# ADC.net
KiCad netlist of a schematic drawn in EAGLE
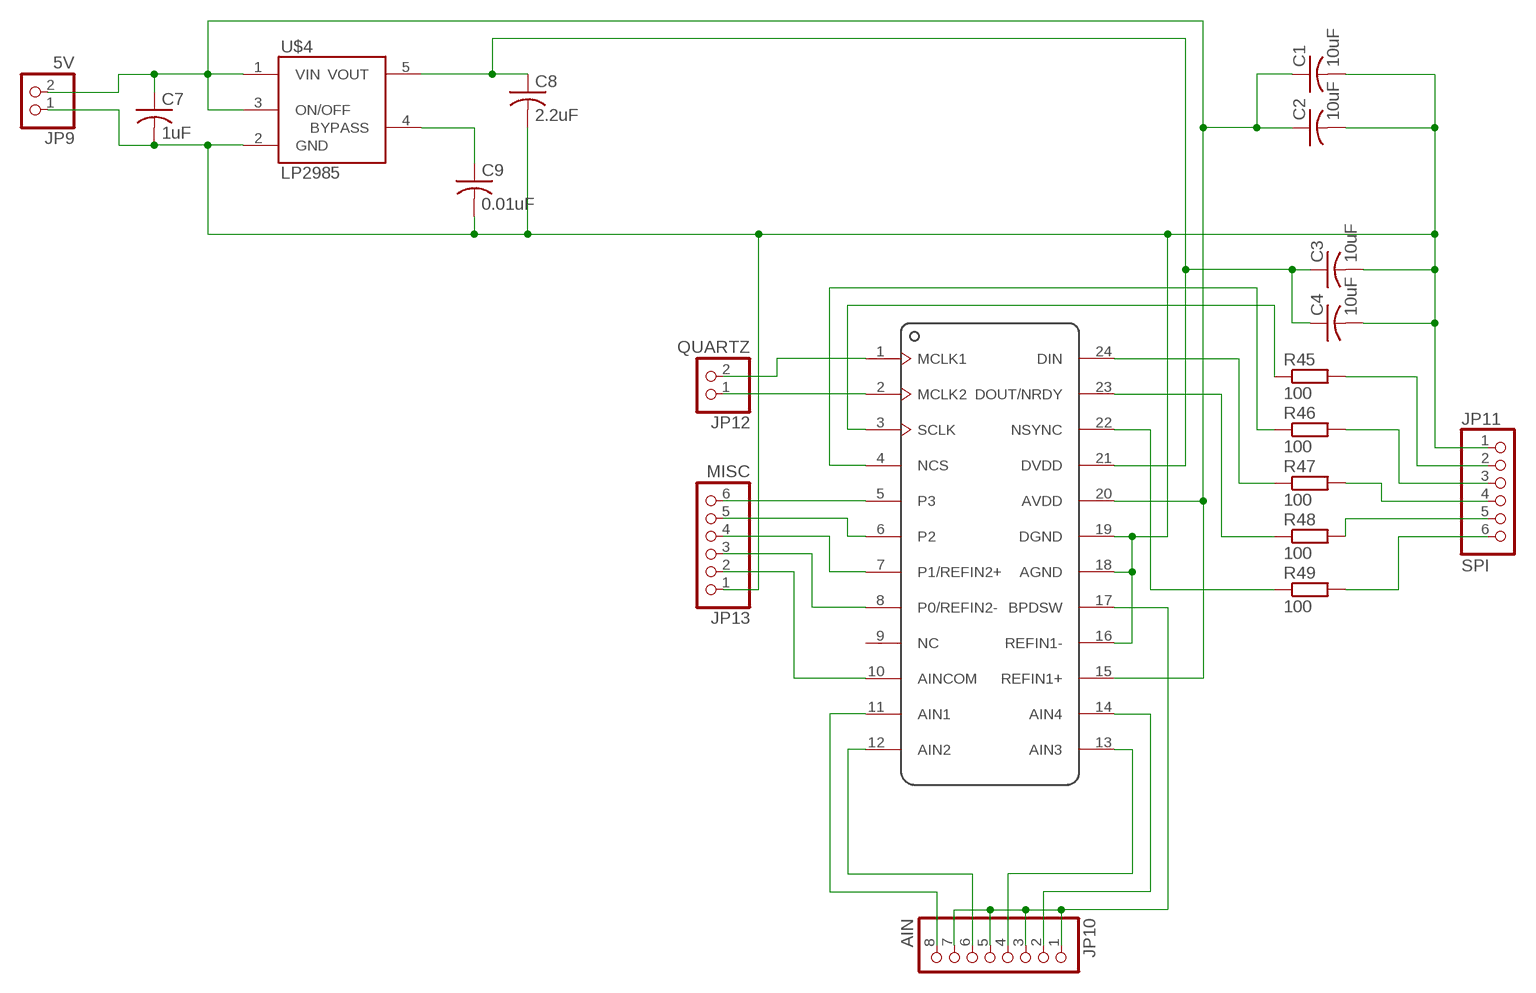
[diagram p0: schematic, sheet 1]

(export (version "E")
  (design (tool "Eeschema 10.0.6"))
  (components
    (comp (ref "C1")
      (value "10uF")
      (footprint "eagle-import:C0603")
      (libsource (lib "eagle-import") (part "C-USC0603"))
    )
    (comp (ref "C2")
      (value "10uF")
      (footprint "eagle-import:C0603")
      (libsource (lib "eagle-import") (part "C-USC0603"))
    )
    (comp (ref "C3")
      (value "10uF")
      (footprint "eagle-import:C0603")
      (libsource (lib "eagle-import") (part "C-USC0603"))
    )
    (comp (ref "C4")
      (value "10uF")
      (footprint "eagle-import:C0603")
      (libsource (lib "eagle-import") (part "C-USC0603"))
    )
    (comp (ref "C7")
      (value "1uF")
      (footprint "eagle-import:C0603")
      (libsource (lib "eagle-import") (part "C-USC0603"))
    )
    (comp (ref "C8")
      (value "2.2uF")
      (footprint "eagle-import:C0603")
      (libsource (lib "eagle-import") (part "C-USC0603"))
    )
    (comp (ref "C9")
      (value "0.01uF")
      (footprint "eagle-import:C0603")
      (libsource (lib "eagle-import") (part "C-USC0603"))
    )
    (comp (ref "JP9")
      (value "5V")
      (footprint "eagle-import:1X02")
      (libsource (lib "eagle-import") (part "PINHD-1X2"))
    )
    (comp (ref "JP10")
      (value "AIN")
      (footprint "eagle-import:1X08")
      (libsource (lib "eagle-import") (part "PINHD-1X8"))
    )
    (comp (ref "JP11")
      (value "SPI")
      (footprint "eagle-import:1X06")
      (libsource (lib "eagle-import") (part "PINHD-1X6"))
    )
    (comp (ref "JP12")
      (value "QUARTZ")
      (footprint "eagle-import:1X02")
      (libsource (lib "eagle-import") (part "PINHD-1X2"))
    )
    (comp (ref "JP13")
      (value "MISC")
      (footprint "eagle-import:1X06")
      (libsource (lib "eagle-import") (part "PINHD-1X6"))
    )
    (comp (ref "R45")
      (value "100")
      (footprint "eagle-import:R1206")
      (libsource (lib "eagle-import") (part "R-EU_R1206"))
    )
    (comp (ref "R46")
      (value "100")
      (footprint "eagle-import:R1206")
      (libsource (lib "eagle-import") (part "R-EU_R1206"))
    )
    (comp (ref "R47")
      (value "100")
      (footprint "eagle-import:R1206")
      (libsource (lib "eagle-import") (part "R-EU_R1206"))
    )
    (comp (ref "R48")
      (value "100")
      (footprint "eagle-import:R1206")
      (libsource (lib "eagle-import") (part "R-EU_R1206"))
    )
    (comp (ref "R49")
      (value "100")
      (footprint "eagle-import:R1206")
      (libsource (lib "eagle-import") (part "R-EU_R1206"))
    )
    (comp (ref "U$3")
      (value "AD7190")
      (footprint "eagle-import:TSSOP24")
      (libsource (lib "eagle-import") (part "AD7190"))
    )
    (comp (ref "U$4")
      (value "LP2985AIM5-3.3")
      (footprint "eagle-import:SOT25")
      (libsource (lib "eagle-import") (part "LP2985AIM5-3.3"))
    )
  )
  (nets
    (net (code "1") (name "Net-(JP11-Pad2)") (class "Default")
      (node (ref "JP11") (pin "2") (pinfunction "2_2") (pintype "passive"))
      (node (ref "R45") (pin "2") (pinfunction "2_2") (pintype "passive"))
    )
    (net (code "2") (name "Net-(JP11-Pad3)") (class "Default")
      (node (ref "JP11") (pin "3") (pinfunction "3_3") (pintype "passive"))
      (node (ref "R46") (pin "2") (pinfunction "2_2") (pintype "passive"))
    )
    (net (code "3") (name "Net-(JP11-Pad4)") (class "Default")
      (node (ref "JP11") (pin "4") (pinfunction "4_4") (pintype "passive"))
      (node (ref "R47") (pin "2") (pinfunction "2_2") (pintype "passive"))
    )
    (net (code "4") (name "Net-(JP11-Pad5)") (class "Default")
      (node (ref "JP11") (pin "5") (pinfunction "5_5") (pintype "passive"))
      (node (ref "R48") (pin "2") (pinfunction "2_2") (pintype "passive"))
    )
    (net (code "5") (name "Net-(JP11-Pad6)") (class "Default")
      (node (ref "JP11") (pin "6") (pinfunction "6_6") (pintype "passive"))
      (node (ref "R49") (pin "2") (pinfunction "2_2") (pintype "passive"))
    )
    (net (code "6") (name "Net-(U$3-AGND)") (class "Default")
      (node (ref "C1") (pin "2") (pinfunction "2_2") (pintype "passive"))
      (node (ref "C2") (pin "2") (pinfunction "2_2") (pintype "passive"))
      (node (ref "C3") (pin "2") (pinfunction "2_2") (pintype "passive"))
      (node (ref "C4") (pin "2") (pinfunction "2_2") (pintype "passive"))
      (node (ref "C7") (pin "2") (pinfunction "2_2") (pintype "passive"))
      (node (ref "C8") (pin "2") (pinfunction "2_2") (pintype "passive"))
      (node (ref "C9") (pin "2") (pinfunction "2_2") (pintype "passive"))
      (node (ref "JP11") (pin "1") (pinfunction "1_1") (pintype "passive"))
      (node (ref "JP13") (pin "1") (pinfunction "1_1") (pintype "passive"))
      (node (ref "JP9") (pin "1") (pinfunction "1_1") (pintype "passive"))
      (node (ref "U$3") (pin "16") (pinfunction "REFIN1-_16") (pintype "bidirectional"))
      (node (ref "U$3") (pin "18") (pinfunction "AGND_18") (pintype "power_in"))
      (node (ref "U$3") (pin "19") (pinfunction "DGND_19") (pintype "power_in"))
      (node (ref "U$4") (pin "2") (pinfunction "GND_2") (pintype "power_in"))
    )
    (net (code "7") (name "Net-(U$3-AIN1)") (class "Default")
      (node (ref "JP10") (pin "8") (pinfunction "8_8") (pintype "passive"))
      (node (ref "U$3") (pin "11") (pinfunction "AIN1_11") (pintype "input"))
    )
    (net (code "8") (name "Net-(U$3-AIN2)") (class "Default")
      (node (ref "JP10") (pin "6") (pinfunction "6_6") (pintype "passive"))
      (node (ref "U$3") (pin "12") (pinfunction "AIN2_12") (pintype "input"))
    )
    (net (code "9") (name "Net-(U$3-AIN3)") (class "Default")
      (node (ref "JP10") (pin "4") (pinfunction "4_4") (pintype "passive"))
      (node (ref "U$3") (pin "13") (pinfunction "AIN3_13") (pintype "input"))
    )
    (net (code "10") (name "Net-(U$3-AIN4)") (class "Default")
      (node (ref "JP10") (pin "2") (pinfunction "2_2") (pintype "passive"))
      (node (ref "U$3") (pin "14") (pinfunction "AIN4_14") (pintype "input"))
    )
    (net (code "11") (name "Net-(U$3-AINCOM)") (class "Default")
      (node (ref "JP13") (pin "2") (pinfunction "2_2") (pintype "passive"))
      (node (ref "U$3") (pin "10") (pinfunction "AINCOM_10") (pintype "input"))
    )
    (net (code "12") (name "Net-(U$3-AVDD)") (class "Default")
      (node (ref "C1") (pin "1") (pinfunction "1_1") (pintype "passive"))
      (node (ref "C2") (pin "1") (pinfunction "1_1") (pintype "passive"))
      (node (ref "C7") (pin "1") (pinfunction "1_1") (pintype "passive"))
      (node (ref "JP9") (pin "2") (pinfunction "2_2") (pintype "passive"))
      (node (ref "U$3") (pin "15") (pinfunction "REFIN1+_15") (pintype "bidirectional"))
      (node (ref "U$3") (pin "20") (pinfunction "AVDD_20") (pintype "power_in"))
      (node (ref "U$4") (pin "1") (pinfunction "VIN_1") (pintype "power_in"))
      (node (ref "U$4") (pin "3") (pinfunction "ON/OFF_3") (pintype "input"))
    )
    (net (code "13") (name "Net-(U$3-BPDSW)") (class "Default")
      (node (ref "JP10") (pin "1") (pinfunction "1_1") (pintype "passive"))
      (node (ref "JP10") (pin "3") (pinfunction "3_3") (pintype "passive"))
      (node (ref "JP10") (pin "5") (pinfunction "5_5") (pintype "passive"))
      (node (ref "JP10") (pin "7") (pinfunction "7_7") (pintype "passive"))
      (node (ref "U$3") (pin "17") (pinfunction "BPDSW_17") (pintype "bidirectional"))
    )
    (net (code "14") (name "Net-(U$3-DIN)") (class "Default")
      (node (ref "R47") (pin "1") (pinfunction "1_1") (pintype "passive"))
      (node (ref "U$3") (pin "24") (pinfunction "DIN_24") (pintype "bidirectional"))
    )
    (net (code "15") (name "Net-(U$3-DOUT{slash}NRDY)") (class "Default")
      (node (ref "R48") (pin "1") (pinfunction "1_1") (pintype "passive"))
      (node (ref "U$3") (pin "23") (pinfunction "DOUT/NRDY_23") (pintype "bidirectional"))
    )
    (net (code "16") (name "Net-(U$3-DVDD)") (class "Default")
      (node (ref "C3") (pin "1") (pinfunction "1_1") (pintype "passive"))
      (node (ref "C4") (pin "1") (pinfunction "1_1") (pintype "passive"))
      (node (ref "C8") (pin "1") (pinfunction "1_1") (pintype "passive"))
      (node (ref "U$3") (pin "21") (pinfunction "DVDD_21") (pintype "power_in"))
      (node (ref "U$4") (pin "5") (pinfunction "VOUT_5") (pintype "power_in"))
    )
    (net (code "17") (name "Net-(U$3-MCLK1)") (class "Default")
      (node (ref "JP12") (pin "2") (pinfunction "2_2") (pintype "passive"))
      (node (ref "U$3") (pin "1") (pinfunction "MCLK1_1") (pintype "input"))
    )
    (net (code "18") (name "Net-(U$3-MCLK2)") (class "Default")
      (node (ref "JP12") (pin "1") (pinfunction "1_1") (pintype "passive"))
      (node (ref "U$3") (pin "2") (pinfunction "MCLK2_2") (pintype "input"))
    )
    (net (code "19") (name "Net-(U$3-NCS)") (class "Default")
      (node (ref "R46") (pin "1") (pinfunction "1_1") (pintype "passive"))
      (node (ref "U$3") (pin "4") (pinfunction "NCS_4") (pintype "bidirectional"))
    )
    (net (code "20") (name "Net-(U$3-NSYNC)") (class "Default")
      (node (ref "R49") (pin "1") (pinfunction "1_1") (pintype "passive"))
      (node (ref "U$3") (pin "22") (pinfunction "NSYNC_22") (pintype "bidirectional"))
    )
    (net (code "21") (name "Net-(U$3-P0{slash}REFIN2-)") (class "Default")
      (node (ref "JP13") (pin "3") (pinfunction "3_3") (pintype "passive"))
      (node (ref "U$3") (pin "8") (pinfunction "P0/REFIN2-_8") (pintype "bidirectional"))
    )
    (net (code "22") (name "Net-(U$3-P1{slash}REFIN2+)") (class "Default")
      (node (ref "JP13") (pin "4") (pinfunction "4_4") (pintype "passive"))
      (node (ref "U$3") (pin "7") (pinfunction "P1/REFIN2+_7") (pintype "bidirectional"))
    )
    (net (code "23") (name "Net-(U$3-P2)") (class "Default")
      (node (ref "JP13") (pin "5") (pinfunction "5_5") (pintype "passive"))
      (node (ref "U$3") (pin "6") (pinfunction "P2_6") (pintype "bidirectional"))
    )
    (net (code "24") (name "Net-(U$3-P3)") (class "Default")
      (node (ref "JP13") (pin "6") (pinfunction "6_6") (pintype "passive"))
      (node (ref "U$3") (pin "5") (pinfunction "P3_5") (pintype "bidirectional"))
    )
    (net (code "25") (name "Net-(U$3-SCLK)") (class "Default")
      (node (ref "R45") (pin "1") (pinfunction "1_1") (pintype "passive"))
      (node (ref "U$3") (pin "3") (pinfunction "SCLK_3") (pintype "bidirectional"))
    )
    (net (code "26") (name "Net-(U$4-BYPASS)") (class "Default")
      (node (ref "C9") (pin "1") (pinfunction "1_1") (pintype "passive"))
      (node (ref "U$4") (pin "4") (pinfunction "BYPASS_4") (pintype "power_in"))
    )
    (net (code "27") (name "unconnected-(U$3-NC-Pad9)") (class "Default")
      (node (ref "U$3") (pin "9") (pinfunction "NC_9") (pintype "no_connect"))
    )
  )
)
